# schematic_ap_copy.net
KiCad netlist of a schematic drawn in EAGLE
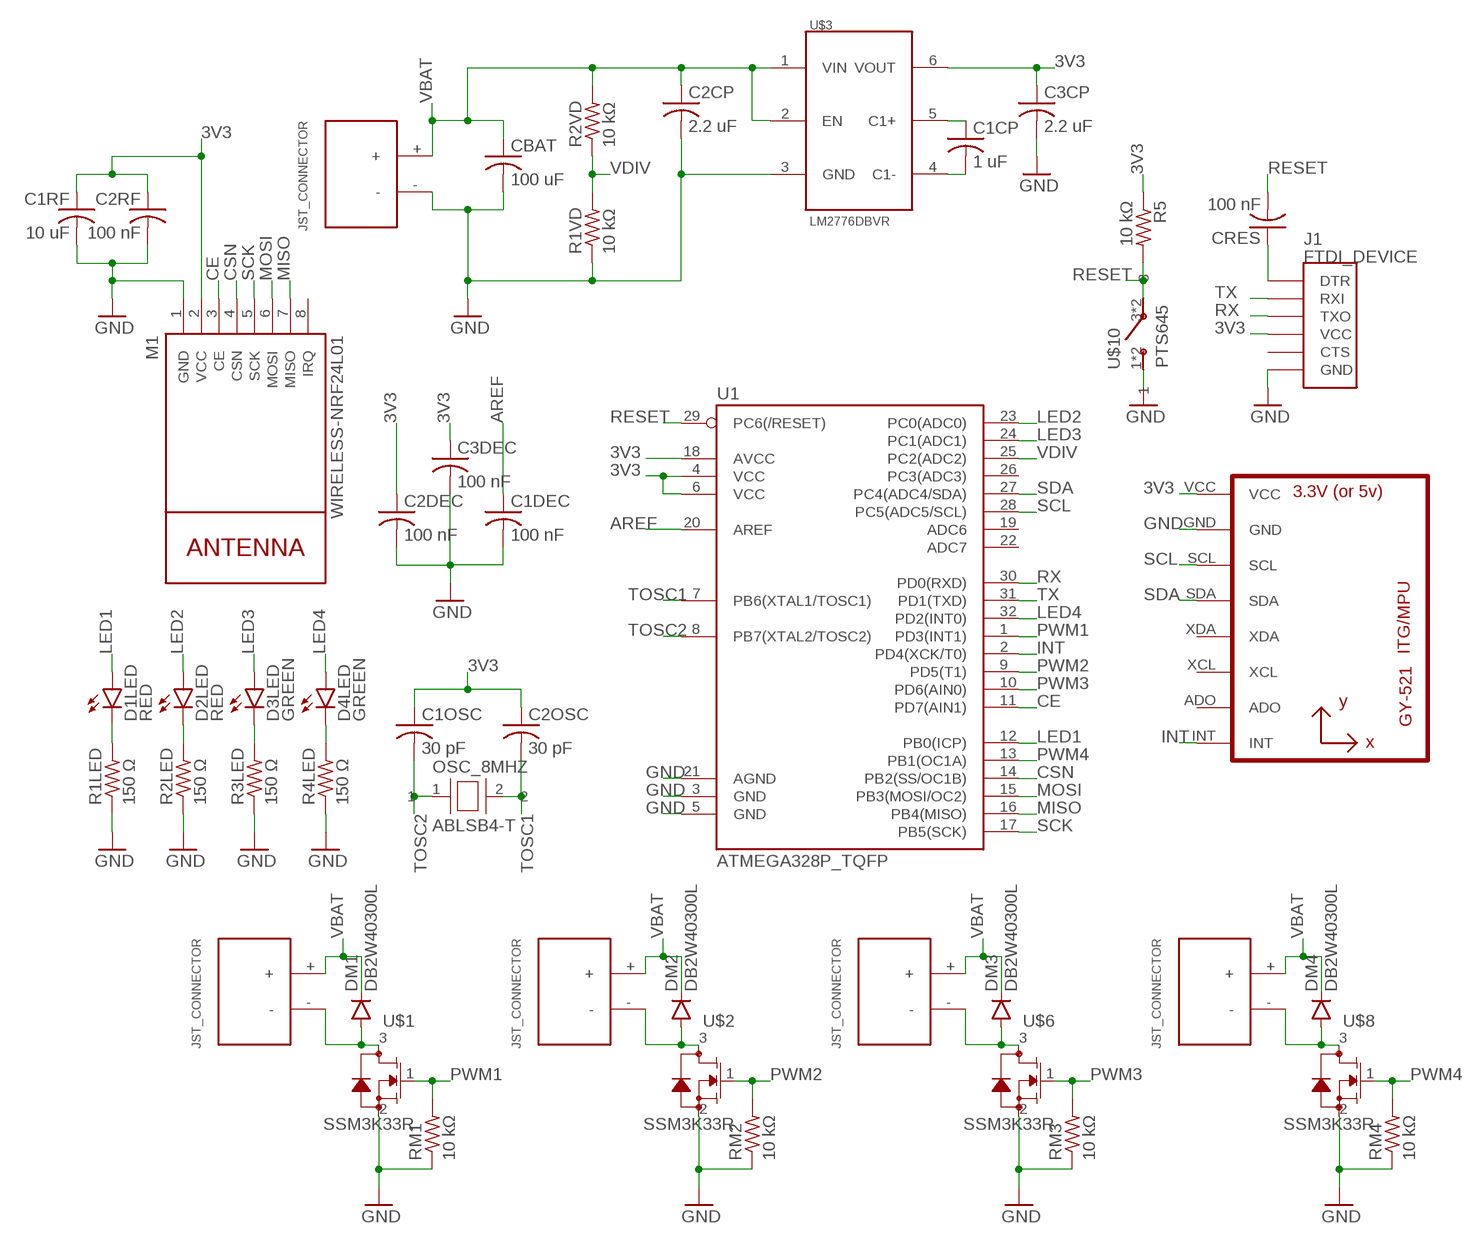
[diagram p0: schematic, sheet 1]

(export (version "E")
  (design (tool "Eeschema 10.0.6"))
  (components
    (comp (ref "C1CP")
      (value "1 uF")
      (footprint "eagle-import:C0603")
      (libsource (lib "eagle-import") (part "C-USC0603"))
    )
    (comp (ref "C1DEC")
      (value "100 nF")
      (footprint "eagle-import:C0603")
      (libsource (lib "eagle-import") (part "C-USC0603"))
    )
    (comp (ref "C1OSC")
      (value "30 pF")
      (footprint "eagle-import:C0603")
      (libsource (lib "eagle-import") (part "C-USC0603"))
    )
    (comp (ref "C1RF")
      (value "10 uF")
      (footprint "eagle-import:C0603")
      (libsource (lib "eagle-import") (part "C-USC0603"))
    )
    (comp (ref "C2CP")
      (value "2.2 uF")
      (footprint "eagle-import:C0603")
      (libsource (lib "eagle-import") (part "C-USC0603"))
    )
    (comp (ref "C2DEC")
      (value "100 nF")
      (footprint "eagle-import:C0603")
      (libsource (lib "eagle-import") (part "C-USC0603"))
    )
    (comp (ref "C2OSC")
      (value "30 pF")
      (footprint "eagle-import:C0603")
      (libsource (lib "eagle-import") (part "C-USC0603"))
    )
    (comp (ref "C2RF")
      (value "100 nF")
      (footprint "eagle-import:C0603")
      (libsource (lib "eagle-import") (part "C-USC0603"))
    )
    (comp (ref "C3CP")
      (value "2.2 uF")
      (footprint "eagle-import:C0603")
      (libsource (lib "eagle-import") (part "C-USC0603"))
    )
    (comp (ref "C3DEC")
      (value "100 nF")
      (footprint "eagle-import:C0603")
      (libsource (lib "eagle-import") (part "C-USC0603"))
    )
    (comp (ref "CBAT")
      (value "100 uF")
      (footprint "eagle-import:C0805")
      (libsource (lib "eagle-import") (part "C-USC0805"))
    )
    (comp (ref "CRES")
      (value "100 nF")
      (footprint "eagle-import:C0603")
      (libsource (lib "eagle-import") (part "C-USC0603"))
    )
    (comp (ref "D1LED")
      (value "RED")
      (footprint "eagle-import:LED-0603")
      (libsource (lib "eagle-import") (part "LED-RED0603"))
    )
    (comp (ref "D2LED")
      (value "RED")
      (footprint "eagle-import:LED-0603")
      (libsource (lib "eagle-import") (part "LED-RED0603"))
    )
    (comp (ref "D3LED")
      (value "GREEN")
      (footprint "eagle-import:LED-0603")
      (libsource (lib "eagle-import") (part "LED-GREEN0603"))
    )
    (comp (ref "D4LED")
      (value "GREEN")
      (footprint "eagle-import:LED-0603")
      (libsource (lib "eagle-import") (part "LED-GREEN0603"))
    )
    (comp (ref "DM1")
      (value "DB2W40300L")
      (footprint "eagle-import:MINI2-F3-B")
      (libsource (lib "eagle-import") (part "DB2W40300L"))
    )
    (comp (ref "DM2")
      (value "DB2W40300L")
      (footprint "eagle-import:MINI2-F3-B")
      (libsource (lib "eagle-import") (part "DB2W40300L"))
    )
    (comp (ref "DM3")
      (value "DB2W40300L")
      (footprint "eagle-import:MINI2-F3-B")
      (libsource (lib "eagle-import") (part "DB2W40300L"))
    )
    (comp (ref "DM4")
      (value "DB2W40300L")
      (footprint "eagle-import:MINI2-F3-B")
      (libsource (lib "eagle-import") (part "DB2W40300L"))
    )
    (comp (ref "J1")
      (value "FTDI_DEVICE")
      (footprint "eagle-import:FTDI_DEVICE_SIDE")
      (libsource (lib "eagle-import") (part "FTDI_DEVICE"))
    )
    (comp (ref "M1")
      (value "WIRELESS-NRF24L01")
      (footprint "eagle-import:WIRELESS-NRF24L01")
      (libsource (lib "eagle-import") (part "WIRELESS-NRF24L01"))
    )
    (comp (ref "OSC_8MHZ")
      (value "ABLSB4-T")
      (footprint "eagle-import:SOT-23")
      (libsource (lib "eagle-import") (part "ABLSB4-T"))
    )
    (comp (ref "R1LED")
      (value "150 Ω")
      (footprint "eagle-import:R0603")
      (libsource (lib "eagle-import") (part "R-US_R0603"))
    )
    (comp (ref "R1VD")
      (value "10 kΩ")
      (footprint "eagle-import:R0603")
      (libsource (lib "eagle-import") (part "R-US_R0603"))
    )
    (comp (ref "R2LED")
      (value "150 Ω")
      (footprint "eagle-import:R0603")
      (libsource (lib "eagle-import") (part "R-US_R0603"))
    )
    (comp (ref "R2VD")
      (value "10 kΩ")
      (footprint "eagle-import:R0603")
      (libsource (lib "eagle-import") (part "R-US_R0603"))
    )
    (comp (ref "R3LED")
      (value "150 Ω")
      (footprint "eagle-import:R0603")
      (libsource (lib "eagle-import") (part "R-US_R0603"))
    )
    (comp (ref "R4LED")
      (value "150 Ω")
      (footprint "eagle-import:R0603")
      (libsource (lib "eagle-import") (part "R-US_R0603"))
    )
    (comp (ref "R5")
      (value "10 kΩ")
      (footprint "eagle-import:R0603")
      (libsource (lib "eagle-import") (part "R-US_R0603"))
    )
    (comp (ref "RM1")
      (value "10 kΩ")
      (footprint "eagle-import:R0603")
      (libsource (lib "eagle-import") (part "R-US_R0603"))
    )
    (comp (ref "RM2")
      (value "10 kΩ")
      (footprint "eagle-import:R0603")
      (libsource (lib "eagle-import") (part "R-US_R0603"))
    )
    (comp (ref "RM3")
      (value "10 kΩ")
      (footprint "eagle-import:R0603")
      (libsource (lib "eagle-import") (part "R-US_R0603"))
    )
    (comp (ref "RM4")
      (value "10 kΩ")
      (footprint "eagle-import:R0603")
      (libsource (lib "eagle-import") (part "R-US_R0603"))
    )
    (comp (ref "U$1")
      (value "SSM3K33R")
      (footprint "eagle-import:SOT-23F")
      (libsource (lib "eagle-import") (part "SSM3K33R"))
    )
    (comp (ref "U$2")
      (value "SSM3K33R")
      (footprint "eagle-import:SOT-23F")
      (libsource (lib "eagle-import") (part "SSM3K33R"))
    )
    (comp (ref "U$3")
      (value "LM2776DBVR")
      (footprint "eagle-import:SOT23-5")
      (libsource (lib "eagle-import") (part "LM2776DBVR"))
    )
    (comp (ref "U$4")
      (value "JST_CONNECTOR_FEMALE")
      (footprint "eagle-import:JST_CONNECTOR_FEMALE")
      (libsource (lib "eagle-import") (part "JST_CONNECTOR_FEMALE"))
    )
    (comp (ref "U$5")
      (value "JST_CONNECTOR_FEMALE")
      (footprint "eagle-import:JST_CONNECTOR_FEMALE")
      (libsource (lib "eagle-import") (part "JST_CONNECTOR_FEMALE"))
    )
    (comp (ref "U$6")
      (value "SSM3K33R")
      (footprint "eagle-import:SOT-23F")
      (libsource (lib "eagle-import") (part "SSM3K33R"))
    )
    (comp (ref "U$7")
      (value "JST_CONNECTOR_FEMALE")
      (footprint "eagle-import:JST_CONNECTOR_FEMALE")
      (libsource (lib "eagle-import") (part "JST_CONNECTOR_FEMALE"))
    )
    (comp (ref "U$8")
      (value "SSM3K33R")
      (footprint "eagle-import:SOT-23F")
      (libsource (lib "eagle-import") (part "SSM3K33R"))
    )
    (comp (ref "U$9")
      (value "JST_CONNECTOR_FEMALE")
      (footprint "eagle-import:JST_CONNECTOR_FEMALE")
      (libsource (lib "eagle-import") (part "JST_CONNECTOR_FEMALE"))
    )
    (comp (ref "U$10")
      (value "PTS645")
      (footprint "eagle-import:SOT-35")
      (libsource (lib "eagle-import") (part "PTS645"))
    )
    (comp (ref "U$11")
      (value "JST_CONNECTOR_FEMALE")
      (footprint "eagle-import:JST_CONNECTOR_FEMALE")
      (libsource (lib "eagle-import") (part "JST_CONNECTOR_FEMALE"))
    )
    (comp (ref "U1")
      (value "ATMEGA328P_TQFP")
      (footprint "eagle-import:TQFP32-08")
      (libsource (lib "eagle-import") (part "ATMEGA328P_TQFP"))
    )
    (comp (ref "U2")
      (value "GY-521MPU6050")
      (footprint "eagle-import:GY-521")
      (libsource (lib "eagle-import") (part "GY-521MPU6050"))
    )
  )
  (nets
    (net (code "1") (name "/3V3") (class "Default")
      (node (ref "C1OSC") (pin "1") (pinfunction "1_1") (pintype "passive"))
      (node (ref "C1RF") (pin "1") (pinfunction "1_1") (pintype "passive"))
      (node (ref "C2DEC") (pin "1") (pinfunction "1_1") (pintype "passive"))
      (node (ref "C2OSC") (pin "1") (pinfunction "1_1") (pintype "passive"))
      (node (ref "C2RF") (pin "1") (pinfunction "1_1") (pintype "passive"))
      (node (ref "C3CP") (pin "1") (pinfunction "1_1") (pintype "passive"))
      (node (ref "C3DEC") (pin "1") (pinfunction "1_1") (pintype "passive"))
      (node (ref "J1") (pin "P$4") (pinfunction "VCC_P$4") (pintype "bidirectional"))
      (node (ref "M1") (pin "2") (pinfunction "VCC_2") (pintype "power_in"))
      (node (ref "R5") (pin "1") (pinfunction "1_1") (pintype "passive"))
      (node (ref "U$3") (pin "6") (pinfunction "VOUT_6") (pintype "bidirectional"))
      (node (ref "U1") (pin "18") (pinfunction "AVCC_18") (pintype "bidirectional"))
      (node (ref "U1") (pin "4") (pinfunction "VCC_4") (pintype "bidirectional"))
      (node (ref "U1") (pin "6") (pinfunction "VCC_6") (pintype "bidirectional"))
      (node (ref "U2") (pin "VCC") (pinfunction "VCC_VCC") (pintype "bidirectional"))
    )
    (net (code "2") (name "/AREF") (class "Default")
      (node (ref "C1DEC") (pin "1") (pinfunction "1_1") (pintype "passive"))
      (node (ref "U1") (pin "20") (pinfunction "AREF_20") (pintype "bidirectional"))
    )
    (net (code "3") (name "/CE") (class "Default")
      (node (ref "M1") (pin "3") (pinfunction "CE_3") (pintype "bidirectional"))
      (node (ref "U1") (pin "11") (pinfunction "PD7(AIN1)_11") (pintype "bidirectional"))
    )
    (net (code "4") (name "/CSN") (class "Default")
      (node (ref "M1") (pin "4") (pinfunction "CSN_4") (pintype "bidirectional"))
      (node (ref "U1") (pin "14") (pinfunction "PB2(SS/OC1B)_14") (pintype "bidirectional"))
    )
    (net (code "5") (name "/INT") (class "Default")
      (node (ref "U1") (pin "2") (pinfunction "PD4(XCK/T0)_2") (pintype "bidirectional"))
      (node (ref "U2") (pin "INT") (pinfunction "INT_INT") (pintype "bidirectional"))
    )
    (net (code "6") (name "/LED1") (class "Default")
      (node (ref "D1LED") (pin "A") (pinfunction "A_A") (pintype "passive"))
      (node (ref "U1") (pin "12") (pinfunction "PB0(ICP)_12") (pintype "bidirectional"))
    )
    (net (code "7") (name "/LED2") (class "Default")
      (node (ref "D2LED") (pin "A") (pinfunction "A_A") (pintype "passive"))
      (node (ref "U1") (pin "23") (pinfunction "PC0(ADC0)_23") (pintype "bidirectional"))
    )
    (net (code "8") (name "/LED3") (class "Default")
      (node (ref "D3LED") (pin "A") (pinfunction "A_A") (pintype "passive"))
      (node (ref "U1") (pin "24") (pinfunction "PC1(ADC1)_24") (pintype "bidirectional"))
    )
    (net (code "9") (name "/LED4") (class "Default")
      (node (ref "D4LED") (pin "A") (pinfunction "A_A") (pintype "passive"))
      (node (ref "U1") (pin "32") (pinfunction "PD2(INT0)_32") (pintype "bidirectional"))
    )
    (net (code "10") (name "/MISO") (class "Default")
      (node (ref "M1") (pin "7") (pinfunction "MISO_7") (pintype "bidirectional"))
      (node (ref "U1") (pin "16") (pinfunction "PB4(MISO)_16") (pintype "bidirectional"))
    )
    (net (code "11") (name "/MOSI") (class "Default")
      (node (ref "M1") (pin "6") (pinfunction "MOSI_6") (pintype "bidirectional"))
      (node (ref "U1") (pin "15") (pinfunction "PB3(MOSI/OC2)_15") (pintype "bidirectional"))
    )
    (net (code "12") (name "/PWM1") (class "Default")
      (node (ref "RM1") (pin "2") (pinfunction "2_2") (pintype "passive"))
      (node (ref "U$1") (pin "1") (pinfunction "1_1") (pintype "bidirectional"))
      (node (ref "U1") (pin "1") (pinfunction "PD3(INT1)_1") (pintype "bidirectional"))
    )
    (net (code "13") (name "/PWM2") (class "Default")
      (node (ref "RM2") (pin "2") (pinfunction "2_2") (pintype "passive"))
      (node (ref "U$2") (pin "1") (pinfunction "1_1") (pintype "bidirectional"))
      (node (ref "U1") (pin "9") (pinfunction "PD5(T1)_9") (pintype "bidirectional"))
    )
    (net (code "14") (name "/PWM3") (class "Default")
      (node (ref "RM3") (pin "2") (pinfunction "2_2") (pintype "passive"))
      (node (ref "U$6") (pin "1") (pinfunction "1_1") (pintype "bidirectional"))
      (node (ref "U1") (pin "10") (pinfunction "PD6(AIN0)_10") (pintype "bidirectional"))
    )
    (net (code "15") (name "/PWM4") (class "Default")
      (node (ref "RM4") (pin "2") (pinfunction "2_2") (pintype "passive"))
      (node (ref "U$8") (pin "1") (pinfunction "1_1") (pintype "bidirectional"))
      (node (ref "U1") (pin "13") (pinfunction "PB1(OC1A)_13") (pintype "bidirectional"))
    )
    (net (code "16") (name "/RESET") (class "Default")
      (node (ref "CRES") (pin "2") (pinfunction "2_2") (pintype "passive"))
      (node (ref "R5") (pin "2") (pinfunction "2_2") (pintype "passive"))
      (node (ref "U$10") (pin "3") (pinfunction "3_3") (pintype "bidirectional"))
      (node (ref "U$10") (pin "4") (pinfunction "3_4") (pintype "bidirectional"))
      (node (ref "U1") (pin "29") (pinfunction "PC6(/RESET)_29") (pintype "bidirectional"))
    )
    (net (code "17") (name "/RX") (class "Default")
      (node (ref "J1") (pin "P$3") (pinfunction "TXO_P$3") (pintype "bidirectional"))
      (node (ref "U1") (pin "30") (pinfunction "PD0(RXD)_30") (pintype "bidirectional"))
    )
    (net (code "18") (name "/SCK") (class "Default")
      (node (ref "M1") (pin "5") (pinfunction "SCK_5") (pintype "bidirectional"))
      (node (ref "U1") (pin "17") (pinfunction "PB5(SCK)_17") (pintype "bidirectional"))
    )
    (net (code "19") (name "/SCL") (class "Default")
      (node (ref "U1") (pin "28") (pinfunction "PC5(ADC5/SCL)_28") (pintype "bidirectional"))
      (node (ref "U2") (pin "SCL") (pinfunction "SCL_SCL") (pintype "bidirectional"))
    )
    (net (code "20") (name "/SDA") (class "Default")
      (node (ref "U1") (pin "27") (pinfunction "PC4(ADC4/SDA)_27") (pintype "bidirectional"))
      (node (ref "U2") (pin "SDA") (pinfunction "SDA_SDA") (pintype "bidirectional"))
    )
    (net (code "21") (name "/TOSC1") (class "Default")
      (node (ref "C2OSC") (pin "2") (pinfunction "2_2") (pintype "passive"))
      (node (ref "OSC_8MHZ") (pin "2") (pinfunction "2_2") (pintype "bidirectional"))
      (node (ref "U1") (pin "7") (pinfunction "PB6(XTAL1/TOSC1)_7") (pintype "bidirectional"))
    )
    (net (code "22") (name "/TOSC2") (class "Default")
      (node (ref "C1OSC") (pin "2") (pinfunction "2_2") (pintype "passive"))
      (node (ref "OSC_8MHZ") (pin "1") (pinfunction "1_1") (pintype "bidirectional"))
      (node (ref "U1") (pin "8") (pinfunction "PB7(XTAL2/TOSC2)_8") (pintype "bidirectional"))
    )
    (net (code "23") (name "/TX") (class "Default")
      (node (ref "J1") (pin "P$2") (pinfunction "RXI_P$2") (pintype "bidirectional"))
      (node (ref "U1") (pin "31") (pinfunction "PD1(TXD)_31") (pintype "bidirectional"))
    )
    (net (code "24") (name "/VBAT") (class "Default")
      (node (ref "C2CP") (pin "1") (pinfunction "1_1") (pintype "passive"))
      (node (ref "CBAT") (pin "1") (pinfunction "1_1") (pintype "passive"))
      (node (ref "DM1") (pin "NEG") (pinfunction "GPIN_NEG") (pintype "passive"))
      (node (ref "DM2") (pin "NEG") (pinfunction "GPIN_NEG") (pintype "passive"))
      (node (ref "DM3") (pin "NEG") (pinfunction "GPIN_NEG") (pintype "passive"))
      (node (ref "DM4") (pin "NEG") (pinfunction "GPIN_NEG") (pintype "passive"))
      (node (ref "R2VD") (pin "2") (pinfunction "2_2") (pintype "passive"))
      (node (ref "U$11") (pin "+") (pinfunction "+_+") (pintype "bidirectional"))
      (node (ref "U$3") (pin "1") (pinfunction "VIN_1") (pintype "bidirectional"))
      (node (ref "U$3") (pin "2") (pinfunction "EN_2") (pintype "bidirectional"))
      (node (ref "U$4") (pin "+") (pinfunction "+_+") (pintype "bidirectional"))
      (node (ref "U$5") (pin "+") (pinfunction "+_+") (pintype "bidirectional"))
      (node (ref "U$7") (pin "+") (pinfunction "+_+") (pintype "bidirectional"))
      (node (ref "U$9") (pin "+") (pinfunction "+_+") (pintype "bidirectional"))
    )
    (net (code "25") (name "/VDIV") (class "Default")
      (node (ref "R1VD") (pin "2") (pinfunction "2_2") (pintype "passive"))
      (node (ref "R2VD") (pin "1") (pinfunction "1_1") (pintype "passive"))
      (node (ref "U1") (pin "25") (pinfunction "PC2(ADC2)_25") (pintype "bidirectional"))
    )
    (net (code "26") (name "GND") (class "Default")
      (node (ref "C1DEC") (pin "2") (pinfunction "2_2") (pintype "passive"))
      (node (ref "C1RF") (pin "2") (pinfunction "2_2") (pintype "passive"))
      (node (ref "C2CP") (pin "2") (pinfunction "2_2") (pintype "passive"))
      (node (ref "C2DEC") (pin "2") (pinfunction "2_2") (pintype "passive"))
      (node (ref "C2RF") (pin "2") (pinfunction "2_2") (pintype "passive"))
      (node (ref "C3CP") (pin "2") (pinfunction "2_2") (pintype "passive"))
      (node (ref "C3DEC") (pin "2") (pinfunction "2_2") (pintype "passive"))
      (node (ref "CBAT") (pin "2") (pinfunction "2_2") (pintype "passive"))
      (node (ref "J1") (pin "P$6") (pinfunction "GND_P$6") (pintype "bidirectional"))
      (node (ref "M1") (pin "1") (pinfunction "GND_1") (pintype "power_in"))
      (node (ref "R1LED") (pin "1") (pinfunction "1_1") (pintype "passive"))
      (node (ref "R1VD") (pin "1") (pinfunction "1_1") (pintype "passive"))
      (node (ref "R2LED") (pin "1") (pinfunction "1_1") (pintype "passive"))
      (node (ref "R3LED") (pin "1") (pinfunction "1_1") (pintype "passive"))
      (node (ref "R4LED") (pin "1") (pinfunction "1_1") (pintype "passive"))
      (node (ref "RM1") (pin "1") (pinfunction "1_1") (pintype "passive"))
      (node (ref "RM2") (pin "1") (pinfunction "1_1") (pintype "passive"))
      (node (ref "RM3") (pin "1") (pinfunction "1_1") (pintype "passive"))
      (node (ref "RM4") (pin "1") (pinfunction "1_1") (pintype "passive"))
      (node (ref "U$1") (pin "2") (pinfunction "2_2") (pintype "bidirectional"))
      (node (ref "U$10") (pin "1") (pinfunction "1_1") (pintype "bidirectional"))
      (node (ref "U$10") (pin "2") (pinfunction "1_2") (pintype "bidirectional"))
      (node (ref "U$11") (pin "-") (pinfunction "-_-") (pintype "bidirectional"))
      (node (ref "U$2") (pin "2") (pinfunction "2_2") (pintype "bidirectional"))
      (node (ref "U$3") (pin "3") (pinfunction "GND_3") (pintype "bidirectional"))
      (node (ref "U$6") (pin "2") (pinfunction "2_2") (pintype "bidirectional"))
      (node (ref "U$8") (pin "2") (pinfunction "2_2") (pintype "bidirectional"))
      (node (ref "U1") (pin "21") (pinfunction "AGND_21") (pintype "bidirectional"))
      (node (ref "U1") (pin "3") (pinfunction "GND_3") (pintype "bidirectional"))
      (node (ref "U1") (pin "5") (pinfunction "GND_5") (pintype "bidirectional"))
      (node (ref "U2") (pin "GND") (pinfunction "GND_GND") (pintype "bidirectional"))
    )
    (net (code "27") (name "Net-(D1LED-PadC)") (class "Default")
      (node (ref "D1LED") (pin "C") (pinfunction "C_C") (pintype "passive"))
      (node (ref "R1LED") (pin "2") (pinfunction "2_2") (pintype "passive"))
    )
    (net (code "28") (name "Net-(D2LED-PadC)") (class "Default")
      (node (ref "D2LED") (pin "C") (pinfunction "C_C") (pintype "passive"))
      (node (ref "R2LED") (pin "2") (pinfunction "2_2") (pintype "passive"))
    )
    (net (code "29") (name "Net-(D3LED-PadC)") (class "Default")
      (node (ref "D3LED") (pin "C") (pinfunction "C_C") (pintype "passive"))
      (node (ref "R3LED") (pin "2") (pinfunction "2_2") (pintype "passive"))
    )
    (net (code "30") (name "Net-(D4LED-PadC)") (class "Default")
      (node (ref "D4LED") (pin "C") (pinfunction "C_C") (pintype "passive"))
      (node (ref "R4LED") (pin "2") (pinfunction "2_2") (pintype "passive"))
    )
    (net (code "31") (name "Net-(DM1-PPIN)") (class "Default")
      (node (ref "DM1") (pin "POS") (pinfunction "PPIN_POS") (pintype "passive"))
      (node (ref "U$1") (pin "3") (pinfunction "3_3") (pintype "bidirectional"))
      (node (ref "U$4") (pin "-") (pinfunction "-_-") (pintype "bidirectional"))
    )
    (net (code "32") (name "Net-(DM2-PPIN)") (class "Default")
      (node (ref "DM2") (pin "POS") (pinfunction "PPIN_POS") (pintype "passive"))
      (node (ref "U$2") (pin "3") (pinfunction "3_3") (pintype "bidirectional"))
      (node (ref "U$5") (pin "-") (pinfunction "-_-") (pintype "bidirectional"))
    )
    (net (code "33") (name "Net-(DM3-PPIN)") (class "Default")
      (node (ref "DM3") (pin "POS") (pinfunction "PPIN_POS") (pintype "passive"))
      (node (ref "U$6") (pin "3") (pinfunction "3_3") (pintype "bidirectional"))
      (node (ref "U$7") (pin "-") (pinfunction "-_-") (pintype "bidirectional"))
    )
    (net (code "34") (name "Net-(DM4-PPIN)") (class "Default")
      (node (ref "DM4") (pin "POS") (pinfunction "PPIN_POS") (pintype "passive"))
      (node (ref "U$8") (pin "3") (pinfunction "3_3") (pintype "bidirectional"))
      (node (ref "U$9") (pin "-") (pinfunction "-_-") (pintype "bidirectional"))
    )
    (net (code "35") (name "Net-(J1-DTR)") (class "Default")
      (node (ref "CRES") (pin "1") (pinfunction "1_1") (pintype "passive"))
      (node (ref "J1") (pin "P$1") (pinfunction "DTR_P$1") (pintype "bidirectional"))
    )
    (net (code "36") (name "Net-(U$3-C1+)") (class "Default")
      (node (ref "C1CP") (pin "1") (pinfunction "1_1") (pintype "passive"))
      (node (ref "U$3") (pin "5") (pinfunction "C1+_5") (pintype "bidirectional"))
    )
    (net (code "37") (name "Net-(U$3-C1-)") (class "Default")
      (node (ref "C1CP") (pin "2") (pinfunction "2_2") (pintype "passive"))
      (node (ref "U$3") (pin "4") (pinfunction "C1-_4") (pintype "bidirectional"))
    )
    (net (code "38") (name "unconnected-(J1-CTS-PadP$5)") (class "Default")
      (node (ref "J1") (pin "P$5") (pinfunction "CTS_P$5") (pintype "bidirectional"))
    )
    (net (code "39") (name "unconnected-(M1-IRQ-Pad8)") (class "Default")
      (node (ref "M1") (pin "8") (pinfunction "IRQ_8") (pintype "bidirectional"))
    )
    (net (code "40") (name "unconnected-(U1-ADC6-Pad19)") (class "Default")
      (node (ref "U1") (pin "19") (pinfunction "ADC6_19") (pintype "bidirectional"))
    )
    (net (code "41") (name "unconnected-(U1-ADC7-Pad22)") (class "Default")
      (node (ref "U1") (pin "22") (pinfunction "ADC7_22") (pintype "bidirectional"))
    )
    (net (code "42") (name "unconnected-(U1-PC3(ADC3)-Pad26)") (class "Default")
      (node (ref "U1") (pin "26") (pinfunction "PC3(ADC3)_26") (pintype "bidirectional"))
    )
    (net (code "43") (name "unconnected-(U2-PadADO)") (class "Default")
      (node (ref "U2") (pin "ADO") (pinfunction "ADO_ADO") (pintype "bidirectional"))
    )
    (net (code "44") (name "unconnected-(U2-PadXCL)") (class "Default")
      (node (ref "U2") (pin "XCL") (pinfunction "XCL_XCL") (pintype "bidirectional"))
    )
    (net (code "45") (name "unconnected-(U2-PadXDA)") (class "Default")
      (node (ref "U2") (pin "XDA") (pinfunction "XDA_XDA") (pintype "bidirectional"))
    )
  )
)
